# Christmas_tree_Schematic.net
KiCad netlist of a schematic drawn in EAGLE
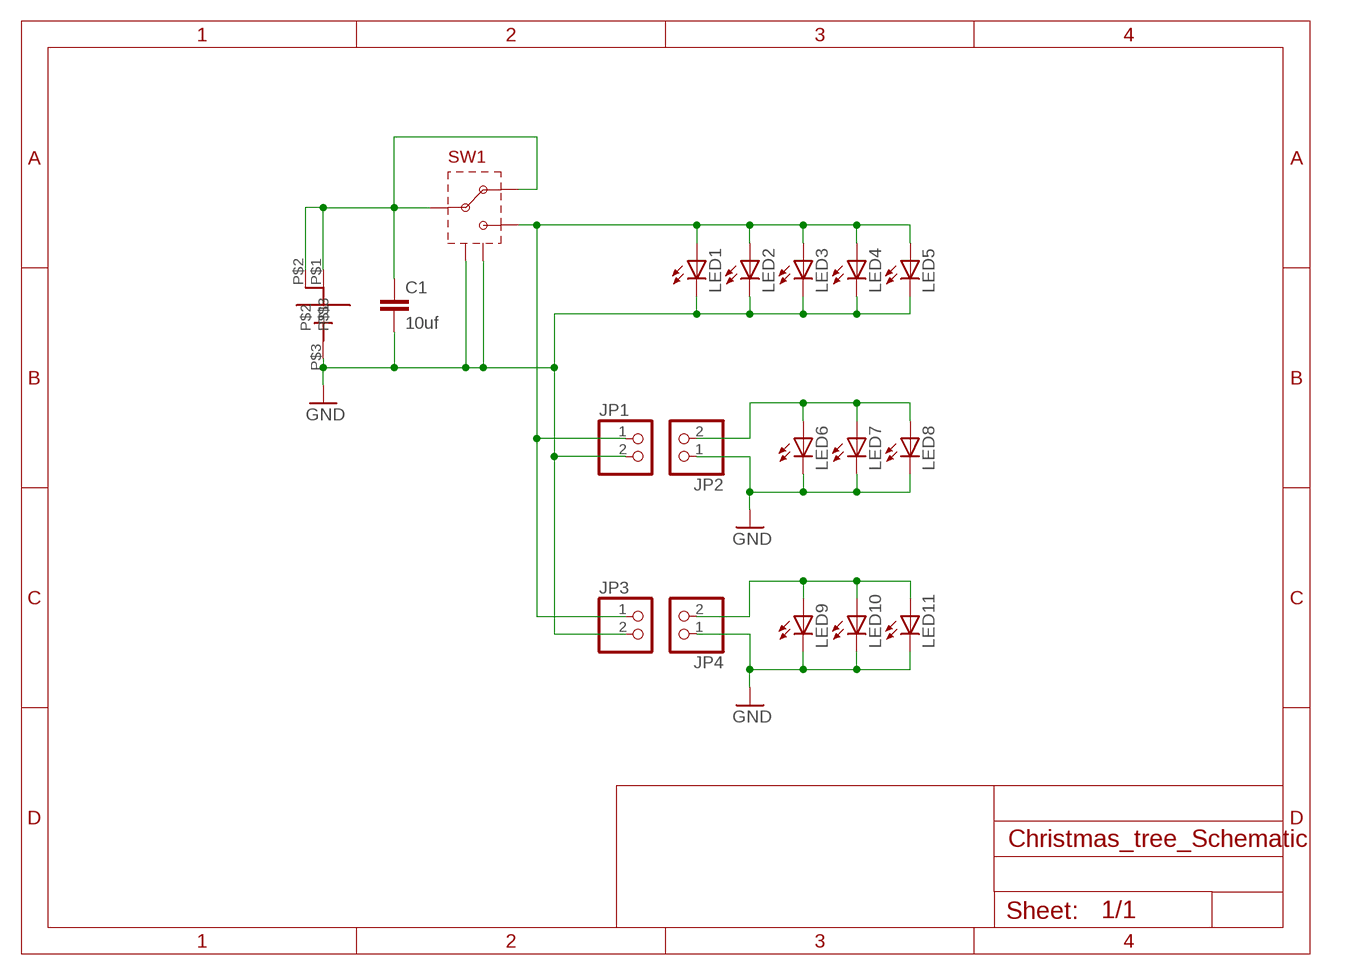
[diagram p0: schematic, sheet 1]

(export (version "E")
  (design (tool "Eeschema 10.0.6"))
  (components
    (comp (ref "BATT")
      (value "CR1220_METAL_HOLDER")
      (footprint "eagle-import:CR1220_METAL_HOLDER")
      (libsource (lib "eagle-import") (part "CR1220_METAL_HOLDER"))
    )
    (comp (ref "C1")
      (value "10uf")
      (footprint "eagle-import:C0805")
      (libsource (lib "eagle-import") (part "C-EUC0805"))
    )
    (comp (ref "JP1")
      (value "PINHD-1X2")
      (footprint "eagle-import:1X02")
      (libsource (lib "eagle-import") (part "PINHD-1X2"))
    )
    (comp (ref "JP2")
      (value "PINHD-1X2")
      (footprint "eagle-import:1X02")
      (libsource (lib "eagle-import") (part "PINHD-1X2"))
    )
    (comp (ref "JP3")
      (value "PINHD-1X2")
      (footprint "eagle-import:1X02")
      (libsource (lib "eagle-import") (part "PINHD-1X2"))
    )
    (comp (ref "JP4")
      (value "PINHD-1X2")
      (footprint "eagle-import:1X02")
      (libsource (lib "eagle-import") (part "PINHD-1X2"))
    )
    (comp (ref "LED1")
      (value "LEDSML0805")
      (footprint "eagle-import:SML0805")
      (libsource (lib "eagle-import") (part "LEDSML0805"))
    )
    (comp (ref "LED2")
      (value "LEDSML0805")
      (footprint "eagle-import:SML0805")
      (libsource (lib "eagle-import") (part "LEDSML0805"))
    )
    (comp (ref "LED3")
      (value "LEDSML0805")
      (footprint "eagle-import:SML0805")
      (libsource (lib "eagle-import") (part "LEDSML0805"))
    )
    (comp (ref "LED4")
      (value "LEDSML0805")
      (footprint "eagle-import:SML0805")
      (libsource (lib "eagle-import") (part "LEDSML0805"))
    )
    (comp (ref "LED5")
      (value "LEDSML0805")
      (footprint "eagle-import:SML0805")
      (libsource (lib "eagle-import") (part "LEDSML0805"))
    )
    (comp (ref "LED6")
      (value "LEDSML0805")
      (footprint "eagle-import:SML0805")
      (libsource (lib "eagle-import") (part "LEDSML0805"))
    )
    (comp (ref "LED7")
      (value "LEDSML0805")
      (footprint "eagle-import:SML0805")
      (libsource (lib "eagle-import") (part "LEDSML0805"))
    )
    (comp (ref "LED8")
      (value "LEDSML0805")
      (footprint "eagle-import:SML0805")
      (libsource (lib "eagle-import") (part "LEDSML0805"))
    )
    (comp (ref "LED9")
      (value "LEDSML0805")
      (footprint "eagle-import:SML0805")
      (libsource (lib "eagle-import") (part "LEDSML0805"))
    )
    (comp (ref "LED10")
      (value "LEDSML0805")
      (footprint "eagle-import:SML0805")
      (libsource (lib "eagle-import") (part "LEDSML0805"))
    )
    (comp (ref "LED11")
      (value "LEDSML0805")
      (footprint "eagle-import:SML0805")
      (libsource (lib "eagle-import") (part "LEDSML0805"))
    )
    (comp (ref "SW1")
      (value "SK-12D07")
      (footprint "eagle-import:SK-12D07")
      (libsource (lib "eagle-import") (part "SK-12D07"))
    )
  )
  (nets
    (net (code "1") (name "GND") (class "Default")
      (node (ref "BATT") (pin "P$3") (pinfunction "P$3_P$3") (pintype "bidirectional"))
      (node (ref "C1") (pin "2") (pinfunction "2_2") (pintype "passive"))
      (node (ref "JP1") (pin "2") (pinfunction "2_2") (pintype "passive"))
      (node (ref "JP2") (pin "1") (pinfunction "1_1") (pintype "passive"))
      (node (ref "JP3") (pin "2") (pinfunction "2_2") (pintype "passive"))
      (node (ref "JP4") (pin "1") (pinfunction "1_1") (pintype "passive"))
      (node (ref "LED1") (pin "C") (pinfunction "C_C") (pintype "passive"))
      (node (ref "LED10") (pin "C") (pinfunction "C_C") (pintype "passive"))
      (node (ref "LED11") (pin "C") (pinfunction "C_C") (pintype "passive"))
      (node (ref "LED2") (pin "C") (pinfunction "C_C") (pintype "passive"))
      (node (ref "LED3") (pin "C") (pinfunction "C_C") (pintype "passive"))
      (node (ref "LED4") (pin "C") (pinfunction "C_C") (pintype "passive"))
      (node (ref "LED5") (pin "C") (pinfunction "C_C") (pintype "passive"))
      (node (ref "LED6") (pin "C") (pinfunction "C_C") (pintype "passive"))
      (node (ref "LED7") (pin "C") (pinfunction "C_C") (pintype "passive"))
      (node (ref "LED8") (pin "C") (pinfunction "C_C") (pintype "passive"))
      (node (ref "LED9") (pin "C") (pinfunction "C_C") (pintype "passive"))
      (node (ref "SW1") (pin "P$4") (pinfunction "P$4_P$4") (pintype "bidirectional"))
      (node (ref "SW1") (pin "P$5") (pinfunction "P$5_P$5") (pintype "bidirectional"))
    )
    (net (code "2") (name "Net-(BATT-PadP$1)") (class "Default")
      (node (ref "BATT") (pin "P$1") (pinfunction "P$1_P$1") (pintype "bidirectional"))
      (node (ref "BATT") (pin "P$2") (pinfunction "P$2_P$2") (pintype "bidirectional"))
      (node (ref "C1") (pin "1") (pinfunction "1_1") (pintype "passive"))
      (node (ref "SW1") (pin "P$1") (pinfunction "P$1_P$1") (pintype "bidirectional"))
      (node (ref "SW1") (pin "P$2") (pinfunction "P$2_P$2") (pintype "bidirectional"))
    )
    (net (code "3") (name "Net-(JP1-Pad1)") (class "Default")
      (node (ref "JP1") (pin "1") (pinfunction "1_1") (pintype "passive"))
      (node (ref "JP3") (pin "1") (pinfunction "1_1") (pintype "passive"))
      (node (ref "LED1") (pin "A") (pinfunction "A_A") (pintype "passive"))
      (node (ref "LED2") (pin "A") (pinfunction "A_A") (pintype "passive"))
      (node (ref "LED3") (pin "A") (pinfunction "A_A") (pintype "passive"))
      (node (ref "LED4") (pin "A") (pinfunction "A_A") (pintype "passive"))
      (node (ref "LED5") (pin "A") (pinfunction "A_A") (pintype "passive"))
      (node (ref "SW1") (pin "P$3") (pinfunction "P$3_P$3") (pintype "bidirectional"))
    )
    (net (code "4") (name "Net-(JP2-Pad2)") (class "Default")
      (node (ref "JP2") (pin "2") (pinfunction "2_2") (pintype "passive"))
      (node (ref "LED6") (pin "A") (pinfunction "A_A") (pintype "passive"))
      (node (ref "LED7") (pin "A") (pinfunction "A_A") (pintype "passive"))
      (node (ref "LED8") (pin "A") (pinfunction "A_A") (pintype "passive"))
    )
    (net (code "5") (name "Net-(JP4-Pad2)") (class "Default")
      (node (ref "JP4") (pin "2") (pinfunction "2_2") (pintype "passive"))
      (node (ref "LED10") (pin "A") (pinfunction "A_A") (pintype "passive"))
      (node (ref "LED11") (pin "A") (pinfunction "A_A") (pintype "passive"))
      (node (ref "LED9") (pin "A") (pinfunction "A_A") (pintype "passive"))
    )
  )
)
